# Double_smd.net
KiCad netlist of a schematic drawn in EAGLE
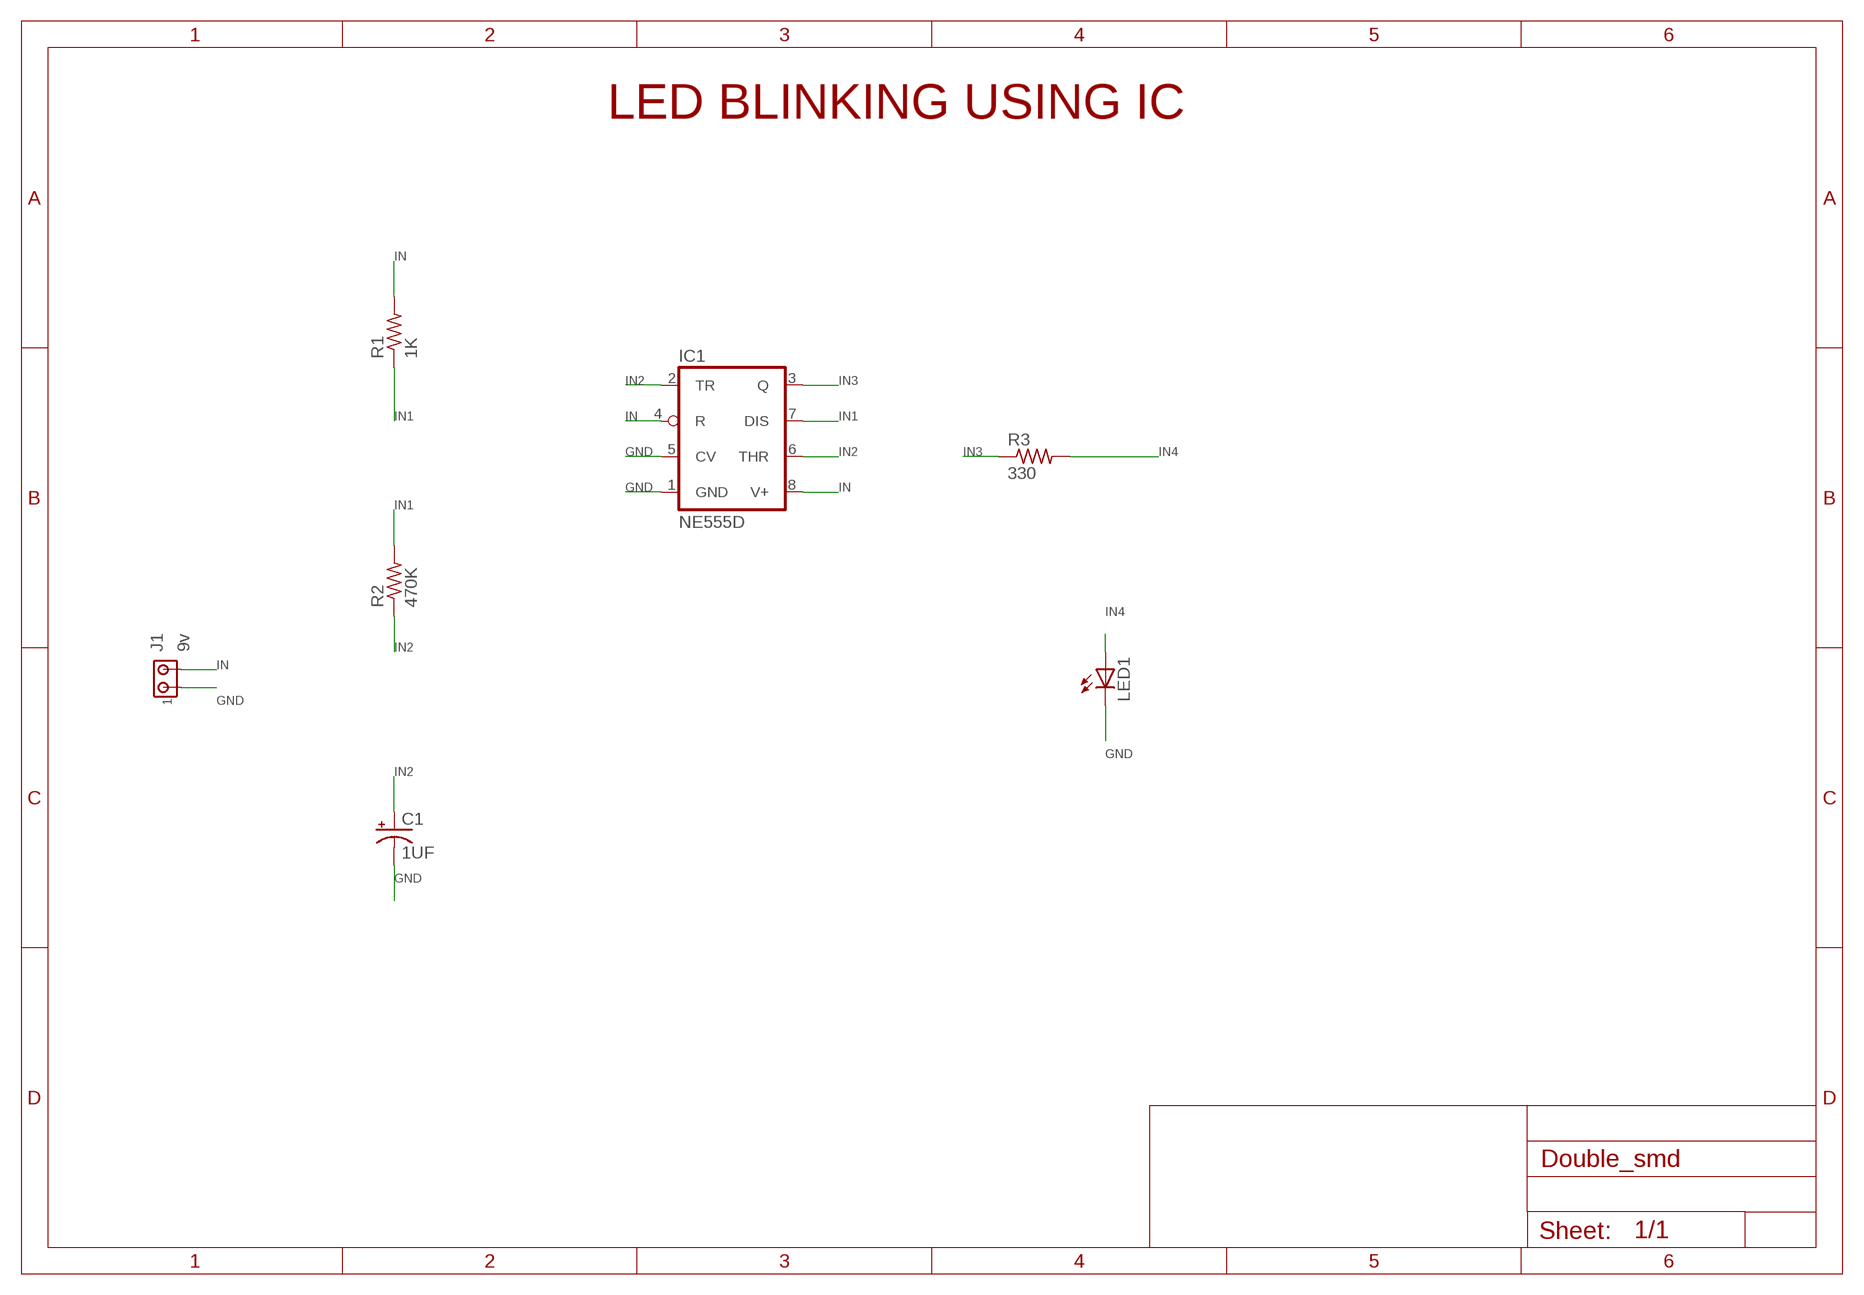
[diagram p0: schematic, sheet 1]

(export (version "E")
  (design (tool "Eeschema 10.0.6"))
  (components
    (comp (ref "C1")
      (value "1UF")
      (footprint "eagle-import:085CS_1R")
      (libsource (lib "eagle-import") (part "CPOL-US085CS-1R"))
    )
    (comp (ref "IC1")
      (value "NE555D")
      (footprint "eagle-import:SO08")
      (libsource (lib "eagle-import") (part "555DNE"))
    )
    (comp (ref "J1")
      (value "9v")
      (footprint "eagle-import:1X2MTA")
      (libsource (lib "eagle-import") (part "MTA02-156"))
    )
    (comp (ref "LED1")
      (value "LED5MM")
      (footprint "eagle-import:LED5MM")
      (libsource (lib "eagle-import") (part "LED5MM"))
    )
    (comp (ref "R1")
      (value "1K")
      (footprint "eagle-import:R0805")
      (libsource (lib "eagle-import") (part "R-US_R0805"))
    )
    (comp (ref "R2")
      (value "470K")
      (footprint "eagle-import:R0805")
      (libsource (lib "eagle-import") (part "R-US_R0805"))
    )
    (comp (ref "R3")
      (value "330")
      (footprint "eagle-import:R0805")
      (libsource (lib "eagle-import") (part "R-US_R0805"))
    )
  )
  (nets
    (net (code "1") (name "/GND") (class "Default")
      (node (ref "C1") (pin "-") (pinfunction "-_-") (pintype "passive"))
      (node (ref "IC1") (pin "1") (pinfunction "GND_1") (pintype "power_in"))
      (node (ref "IC1") (pin "5") (pinfunction "CV_5") (pintype "input"))
      (node (ref "J1") (pin "1") (pinfunction "1_1") (pintype "passive"))
      (node (ref "LED1") (pin "K") (pinfunction "C_K") (pintype "passive"))
    )
    (net (code "2") (name "/IN") (class "Default")
      (node (ref "IC1") (pin "4") (pinfunction "R_4") (pintype "input"))
      (node (ref "IC1") (pin "8") (pinfunction "V+_8") (pintype "power_in"))
      (node (ref "J1") (pin "2") (pinfunction "2_2") (pintype "passive"))
      (node (ref "R1") (pin "2") (pinfunction "2_2") (pintype "passive"))
    )
    (net (code "3") (name "/IN1") (class "Default")
      (node (ref "IC1") (pin "7") (pinfunction "DIS_7") (pintype "input"))
      (node (ref "R1") (pin "1") (pinfunction "1_1") (pintype "passive"))
      (node (ref "R2") (pin "2") (pinfunction "2_2") (pintype "passive"))
    )
    (net (code "4") (name "/IN2") (class "Default")
      (node (ref "C1") (pin "+") (pinfunction "+_+") (pintype "passive"))
      (node (ref "IC1") (pin "2") (pinfunction "TR_2") (pintype "input"))
      (node (ref "IC1") (pin "6") (pinfunction "THR_6") (pintype "input"))
      (node (ref "R2") (pin "1") (pinfunction "1_1") (pintype "passive"))
    )
    (net (code "5") (name "/IN3") (class "Default")
      (node (ref "IC1") (pin "3") (pinfunction "Q_3") (pintype "output"))
      (node (ref "R3") (pin "1") (pinfunction "1_1") (pintype "passive"))
    )
    (net (code "6") (name "/IN4") (class "Default")
      (node (ref "LED1") (pin "A") (pinfunction "A_A") (pintype "passive"))
      (node (ref "R3") (pin "2") (pinfunction "2_2") (pintype "passive"))
    )
  )
)
